# Power_management.net
KiCad netlist of a schematic drawn in Altium Designer
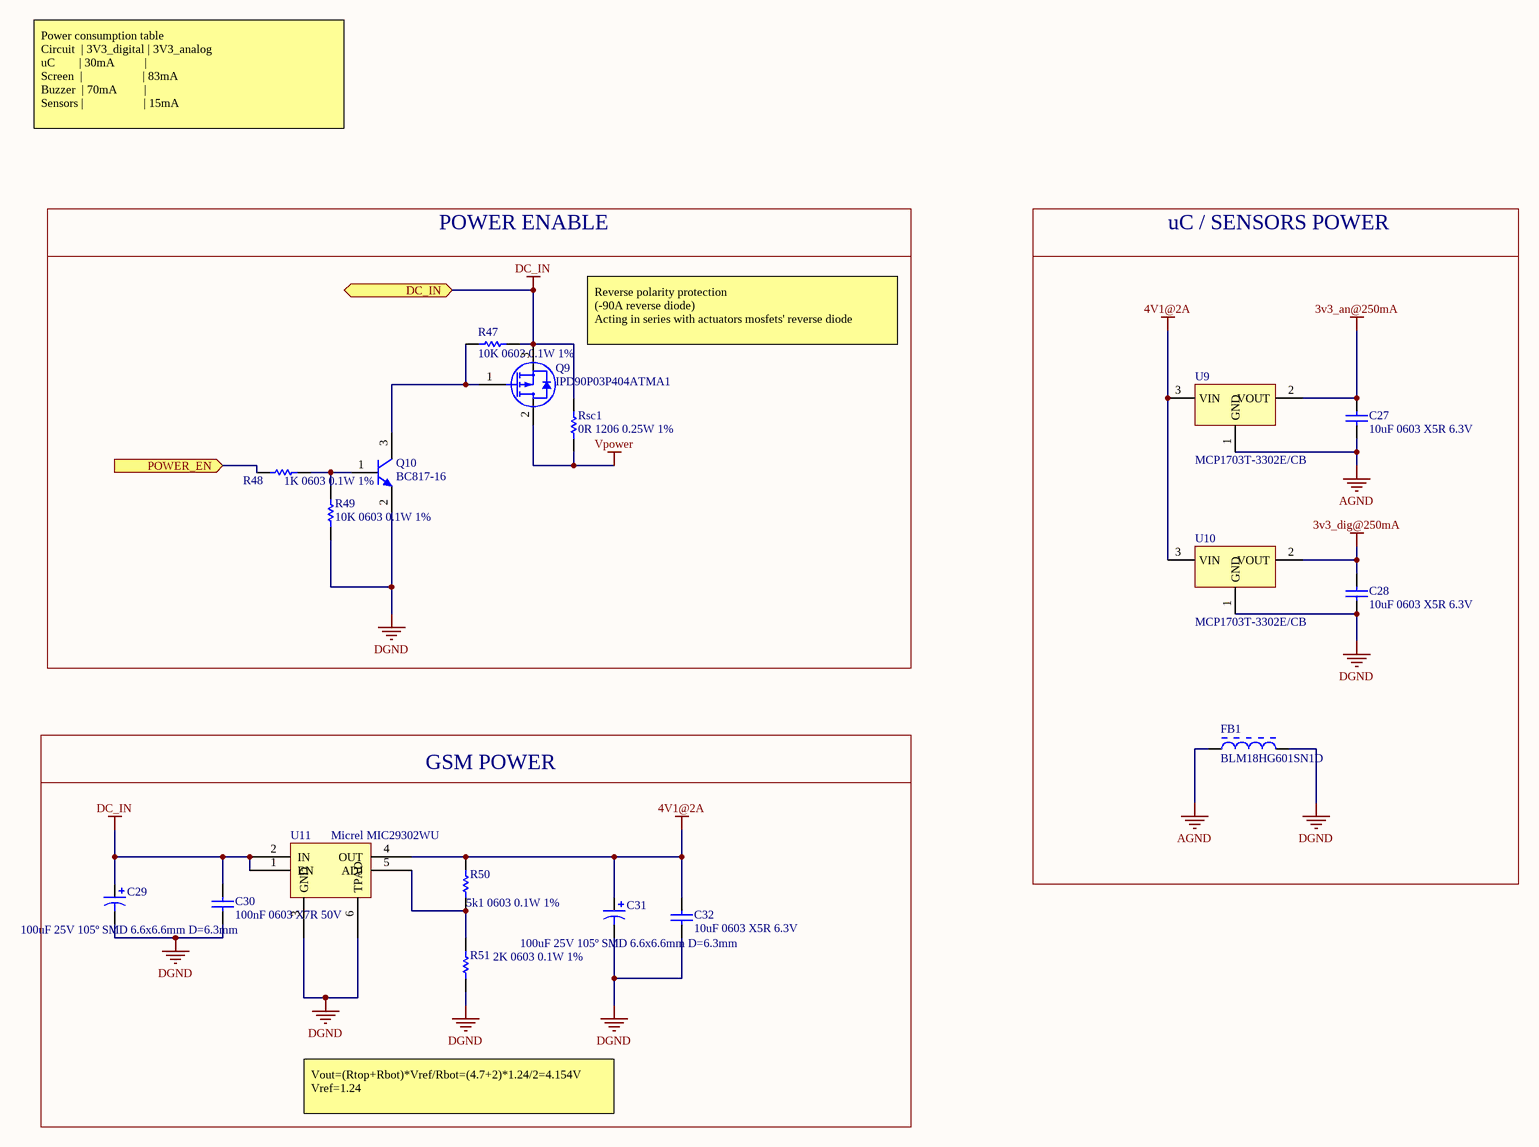
[diagram p0: Power_management.SchDoc]

(export (version "E")
  (design (tool "Eeschema 10.0.6"))
  (components
    (comp (ref "C27")
      (value "10uF 0603 X5R 6.3V")
      (footprint "CAPC1608X60X35NL10T15")
      (libsource (lib "CommunityVault") (part "CMP-121364-8"))
    )
    (comp (ref "C28")
      (value "10uF 0603 X5R 6.3V")
      (footprint "CAPC1608X60X35NL10T15")
      (libsource (lib "CommunityVault") (part "CMP-121364-8"))
    )
    (comp (ref "C29")
      (value "100uF 25V 105º SMD 6.6x6.6mm D=6.3mm")
      (footprint "PCB-5eg0a5nygcrzw5ibm1j9-1")
      (fields (field (name "MANUFACTURER PART NUMBER") "VZL101M1ETR-0607") (field (name "TOLERANCE") "20%"))
      (libsource (lib "CommunityVault") (part "CMP-a6d16ad512617916-1"))
    )
    (comp (ref "C30")
      (value "100nF 0603 X7R 50V")
      (footprint "CAPC1608X60X35NL10T15")
      (description "100nF 0603 X7R 25V")
      (libsource (lib "CommunityVault") (part "CMP-c41a0d2b65641bdd-3"))
    )
    (comp (ref "C31")
      (value "100uF 25V 105º SMD 6.6x6.6mm D=6.3mm")
      (footprint "PCB-5eg0a5nygcrzw5ibm1j9-1")
      (fields (field (name "MANUFACTURER PART NUMBER") "VZL101M1ETR-0607") (field (name "TOLERANCE") "20%"))
      (libsource (lib "CommunityVault") (part "CMP-a6d16ad512617916-1"))
    )
    (comp (ref "C32")
      (value "10uF 0603 X5R 6.3V")
      (footprint "CAPC1608X60X35NL10T15")
      (libsource (lib "CommunityVault") (part "CMP-121364-8"))
    )
    (comp (ref "FB1")
      (value "BLM18HG601SN1D")
      (footprint "MURA-BLM18-F-H1-CHIP-2_V")
      (libsource (lib "CommunityVault") (part "CMP-19299602-3"))
    )
    (comp (ref "Q9")
      (value "IPD90P03P404ATMA1")
      (footprint "DPAK IPD90P03P404ATMA1")
      (description "Single P-Channel 30 V 4.5 mOhm 100 nC OptiMOS Power Mosfet - TO-252-3-11")
      (libsource (lib "CommunityVault") (part "CMP-3103264-6"))
    )
    (comp (ref "Q10")
      (value "BC817-16")
      (footprint "PCB-856332-1")
      (description "TRANS NPN 45V 500mA SMD SOT23-3")
      (libsource (lib "CommunityVault") (part "CMP-856332-3"))
    )
    (comp (ref "R47")
      (value "10K 0603 0.1W 1%")
      (footprint "RESC1609X55X30ML10T20")
      (fields (field (name "TOLERANCE") "1%"))
      (libsource (lib "CommunityVault") (part "CMP-4716590-9"))
    )
    (comp (ref "R48")
      (value "1K 0603 0.1W 1%")
      (footprint "RESC1609X55X30ML10T20")
      (fields (field (name "MANUFACTURER PART NUMBER") "CR0603-FX-1001ELF"))
      (libsource (lib "CommunityVault") (part "CMP-a61f6f36030f79d8-4"))
    )
    (comp (ref "R49")
      (value "10K 0603 0.1W 1%")
      (footprint "RESC1609X55X30ML10T20")
      (fields (field (name "TOLERANCE") "1%"))
      (libsource (lib "CommunityVault") (part "CMP-4716590-9"))
    )
    (comp (ref "R50")
      (value "5k1 0603 0.1W 1%")
      (footprint "RESC1609X55X30ML10T20")
      (fields (field (name "TOLERANCE") "1%"))
      (libsource (lib "CommunityVault") (part "CMP-3655986-6"))
    )
    (comp (ref "R51")
      (value "2K 0603 0.1W 1%")
      (footprint "RESC1609X55X30ML10T20")
      (fields (field (name "TOLERANCE") "1%"))
      (libsource (lib "CommunityVault") (part "CMP-3655986-6"))
    )
    (comp (ref "Rsc1")
      (value "0R 1206 0.25W 1%")
      (footprint "PCB-sxvxwfnl72ysl1kmtzgv-1")
      (fields (field (name "MANUFACTURER PART NUMBER") "RC1206JR-070RL"))
      (libsource (lib "CommunityVault") (part "CMP-3f1bf473a47ce0dc-5"))
    )
    (comp (ref "U9")
      (value "MCP1703T-3302E/CB")
      (footprint "SOT-23A-CB3_L")
      (libsource (lib "CommunityVault") (part "CMP-1493313-4"))
    )
    (comp (ref "U10")
      (value "MCP1703T-3302E/CB")
      (footprint "SOT-23A-CB3_L")
      (libsource (lib "CommunityVault") (part "CMP-1493313-4"))
    )
    (comp (ref "U11")
      (value "Micrel MIC29302WU")
      (footprint "TI-KTT5_N")
      (description "MIC29302 Series 3 A 1.24 to 26 V ADJ Output Voltage LDO Regulator - TO-263-5")
      (libsource (lib "CommunityVault") (part "SYM--116"))
    )
  )
  (nets
    (net (code "1") (name "/POWER_EN") (class "Default")
      (node (ref "R48") (pin "1") (pinfunction "1_1") (pintype "passive"))
    )
    (net (code "2") (name "3v3_an@250mA") (class "Default")
      (node (ref "C27") (pin "2") (pinfunction "2_2") (pintype "passive"))
      (node (ref "U9") (pin "2") (pinfunction "VOUT_2") (pintype "power_in"))
    )
    (net (code "3") (name "3v3_dig@250mA") (class "Default")
      (node (ref "C28") (pin "2") (pinfunction "2_2") (pintype "passive"))
      (node (ref "U10") (pin "2") (pinfunction "VOUT_2") (pintype "power_in"))
    )
    (net (code "4") (name "4V1@2A") (class "Default")
      (node (ref "C31") (pin "1") (pinfunction "1_1") (pintype "passive"))
      (node (ref "C32") (pin "2") (pinfunction "2_2") (pintype "passive"))
      (node (ref "R50") (pin "2") (pinfunction "2_2") (pintype "passive"))
      (node (ref "U10") (pin "3") (pinfunction "VIN_3") (pintype "power_in"))
      (node (ref "U11") (pin "4") (pinfunction "OUT_4") (pintype "passive"))
      (node (ref "U9") (pin "3") (pinfunction "VIN_3") (pintype "power_in"))
    )
    (net (code "5") (name "AGND") (class "Default")
      (node (ref "C27") (pin "1") (pinfunction "1_1") (pintype "passive"))
      (node (ref "FB1") (pin "1") (pinfunction "1_1") (pintype "passive"))
      (node (ref "U9") (pin "1") (pinfunction "GND_1") (pintype "power_in"))
    )
    (net (code "6") (name "DC_IN") (class "Default")
      (node (ref "C29") (pin "1") (pinfunction "1_1") (pintype "passive"))
      (node (ref "C30") (pin "2") (pinfunction "2_2") (pintype "passive"))
      (node (ref "Q9") (pin "3") (pinfunction "S_3") (pintype "passive"))
      (node (ref "R47") (pin "2") (pinfunction "2_2") (pintype "passive"))
      (node (ref "Rsc1") (pin "2") (pinfunction "2_2") (pintype "passive"))
      (node (ref "U11") (pin "1") (pinfunction "EN_1") (pintype "passive"))
      (node (ref "U11") (pin "2") (pinfunction "IN_2") (pintype "passive"))
    )
    (net (code "7") (name "DGND") (class "Default")
      (node (ref "C28") (pin "1") (pinfunction "1_1") (pintype "passive"))
      (node (ref "C29") (pin "2") (pinfunction "2_2") (pintype "passive"))
      (node (ref "C30") (pin "1") (pinfunction "1_1") (pintype "passive"))
      (node (ref "C31") (pin "2") (pinfunction "2_2") (pintype "passive"))
      (node (ref "C32") (pin "1") (pinfunction "1_1") (pintype "passive"))
      (node (ref "FB1") (pin "2") (pinfunction "2_2") (pintype "passive"))
      (node (ref "Q10") (pin "2") (pinfunction "E_2") (pintype "passive"))
      (node (ref "R49") (pin "2") (pinfunction "2_2") (pintype "passive"))
      (node (ref "R51") (pin "1") (pinfunction "1_1") (pintype "passive"))
      (node (ref "U10") (pin "1") (pinfunction "GND_1") (pintype "power_in"))
      (node (ref "U11") (pin "3") (pinfunction "GND_3") (pintype "passive"))
      (node (ref "U11") (pin "6") (pinfunction "TPAD_6") (pintype "passive"))
    )
    (net (code "8") (name "Net-(Q10-B)") (class "Default")
      (node (ref "Q10") (pin "1") (pinfunction "B_1") (pintype "passive"))
      (node (ref "R48") (pin "2") (pinfunction "2_2") (pintype "passive"))
      (node (ref "R49") (pin "1") (pinfunction "1_1") (pintype "passive"))
    )
    (net (code "9") (name "Net-(Q10-C)") (class "Default")
      (node (ref "Q10") (pin "3") (pinfunction "C_3") (pintype "passive"))
      (node (ref "Q9") (pin "1") (pinfunction "G_1") (pintype "passive"))
      (node (ref "R47") (pin "1") (pinfunction "1_1") (pintype "passive"))
    )
    (net (code "10") (name "Net-(U11-ADJ)") (class "Default")
      (node (ref "R50") (pin "1") (pinfunction "1_1") (pintype "passive"))
      (node (ref "R51") (pin "2") (pinfunction "2_2") (pintype "passive"))
      (node (ref "U11") (pin "5") (pinfunction "ADJ_5") (pintype "passive"))
    )
    (net (code "11") (name "Vpower") (class "Default")
      (node (ref "Q9") (pin "2") (pinfunction "D_2") (pintype "passive"))
      (node (ref "Rsc1") (pin "1") (pinfunction "1_1") (pintype "passive"))
    )
  )
)
